# USB_TO_UART.net
KiCad netlist of a schematic drawn in Altium Designer
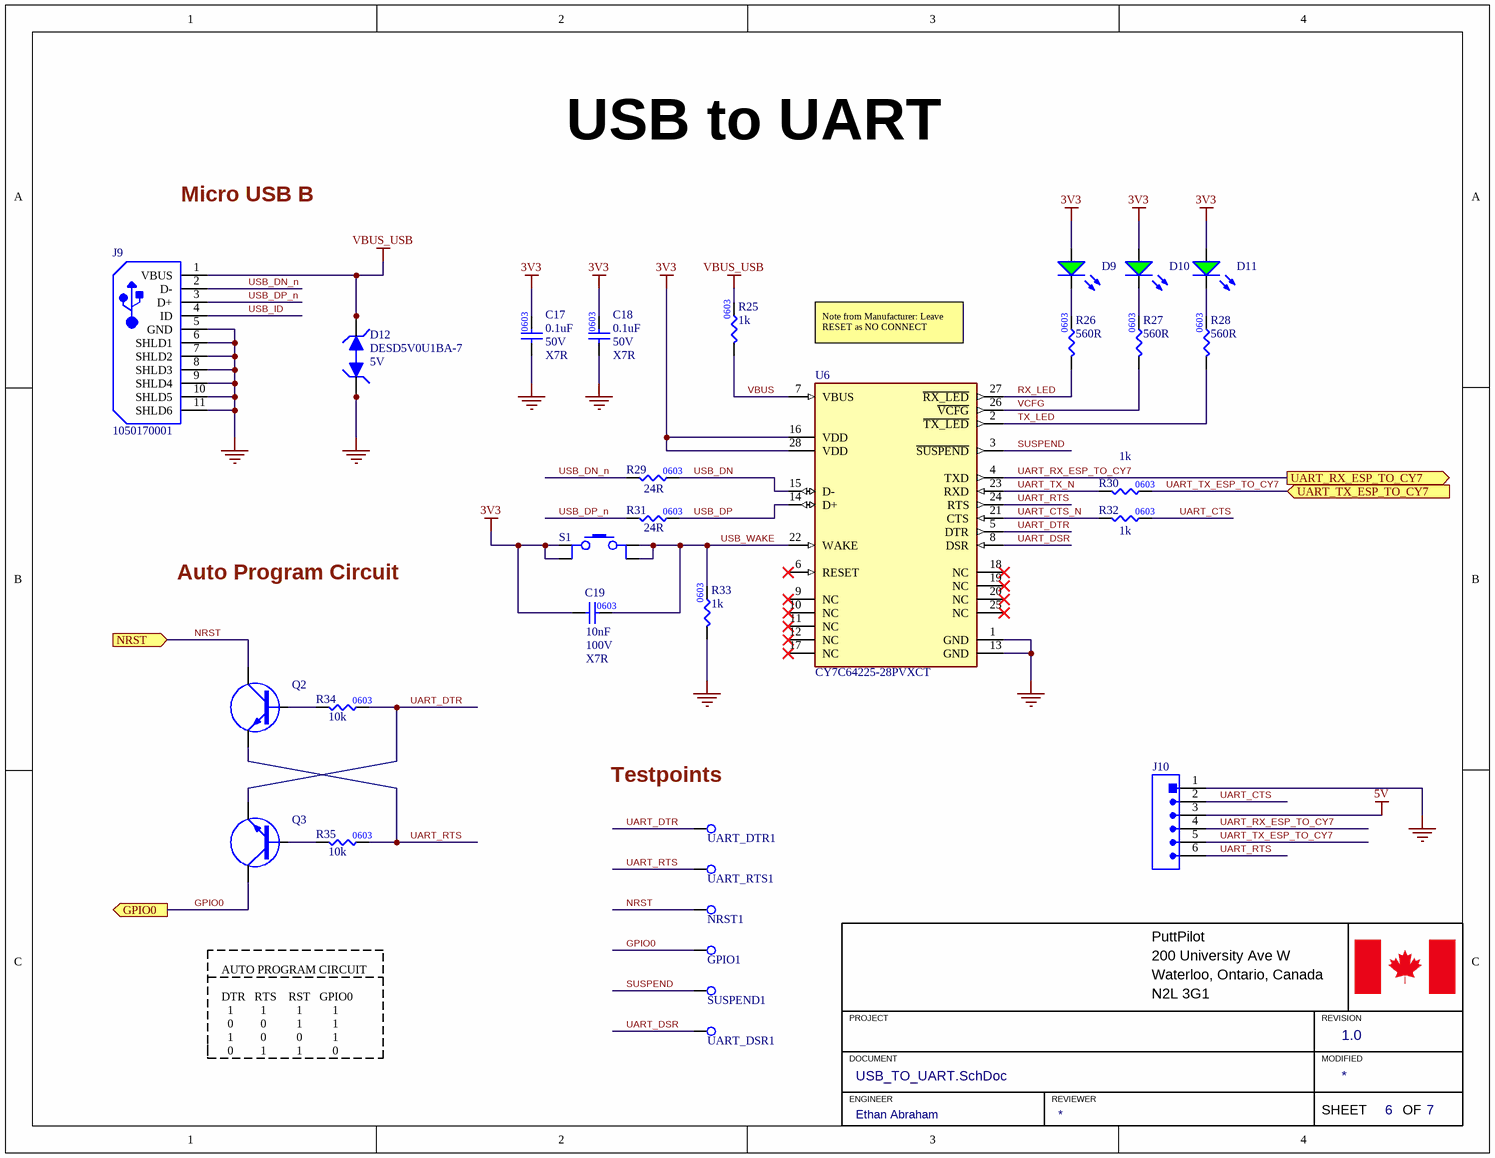
[diagram p0: USB_TO_UART.SchDoc]

(export (version "E")
  (design (tool "Eeschema 10.0.6"))
  (components
    (comp (ref "C17")
      (value "GCJ188R71H104KA12D")
      (footprint ".CAP_0603")
      (description "CAP CER 0.1uF 50V X7R 0603")
      (fields
        (field (name "MANUFACTURER") "Murata")
        (field (name "TEMPERATURE CHARACTERISTICS CODE") "X7R")
        (field (name "RATED DC VOLTAGE (URDC)") "50V")
        (field (name "CAPACITANCE") "0.1uF")
      )
      (libsource (lib "PuttPilot") (part "GCJ188R71H104KA12D"))
    )
    (comp (ref "C18")
      (value "GCJ188R71H104KA12D")
      (footprint ".CAP_0603")
      (description "CAP CER 0.1uF 50V X7R 0603")
      (fields
        (field (name "MANUFACTURER") "Murata")
        (field (name "TEMPERATURE CHARACTERISTICS CODE") "X7R")
        (field (name "RATED DC VOLTAGE (URDC)") "50V")
        (field (name "CAPACITANCE") "0.1uF")
      )
      (libsource (lib "PuttPilot") (part "GCJ188R71H104KA12D"))
    )
    (comp (ref "C19")
      (value "GCM188R72A103KA37D")
      (footprint ".CAP_0603")
      (description "CAP CER 0.01uF 100V X7R")
      (fields
        (field (name "MANUFACTURER") "Murata")
        (field (name "TOLERANCE") "10%")
        (field (name "DIELECTRIC") "X7R")
        (field (name "VOLTAGE RATING") "100V")
        (field (name "CAPACITANCE") "10nF")
      )
      (libsource (lib "PuttPilot") (part "GCM188R72A103KA37D"))
    )
    (comp (ref "D9")
      (value "LTST-C191KGKT")
      (footprint ".LED_0603")
      (description "LED GREEN 2V 0603")
      (fields (field (name "MANUFACTURER") "Vishay Lite-On"))
      (libsource (lib "PuttPilot") (part "LTST-C191KGKT"))
    )
    (comp (ref "D10")
      (value "LTST-C191KGKT")
      (footprint ".LED_0603")
      (description "LED GREEN 2V 0603")
      (fields (field (name "MANUFACTURER") "Vishay Lite-On"))
      (libsource (lib "PuttPilot") (part "LTST-C191KGKT"))
    )
    (comp (ref "D11")
      (value "LTST-C191KGKT")
      (footprint ".LED_0603")
      (description "LED GREEN 2V 0603")
      (fields (field (name "MANUFACTURER") "Vishay Lite-On"))
      (libsource (lib "PuttPilot") (part "LTST-C191KGKT"))
    )
    (comp (ref "D12")
      (value "DESD5V0U1BA-7")
      (footprint "DESD5V0U1BA-7")
      (description "TVS DIODE 5VWM")
      (fields (field (name "MANUFACTURER") "Diodes") (field (name "REP PK REVERSE VOLTAGE-MAX") "5V"))
      (libsource (lib "PuttPilot") (part "DESD5V0U1BA-7"))
    )
    (comp (ref "GPIO1")
      (value "RCWCTE")
      (footprint "RCWCTE")
      (description "SMT Test Point")
      (fields (field (name "MANUFACTURER") "KOA Speer"))
      (libsource (lib "PuttPilot") (part "RCWCTE"))
    )
    (comp (ref "J9")
      (value "1050170001")
      (footprint "USB_MICRO_B")
      (description "CONN USB MICRO B R/A")
      (fields (field (name "MANUFACTURER") "Molex"))
      (libsource (lib "PuttPilot") (part "1050170001"))
    )
    (comp (ref "J10")
      (value "PRPC040SAAN-RC_POS6")
      (footprint "HEADER_6POS_2.54MM")
      (description "CONN HEADER VERT 6POS 2.54MM")
      (libsource (lib "PuttPilot") (part "PRPC040SAAN-RC_POS6"))
    )
    (comp (ref "NRST1")
      (value "RCWCTE")
      (footprint "RCWCTE")
      (description "SMT Test Point")
      (fields (field (name "MANUFACTURER") "KOA Speer"))
      (libsource (lib "PuttPilot") (part "RCWCTE"))
    )
    (comp (ref "Q2")
      (value "MMBT2222A-7-F")
      (footprint ".SOT-23-3")
      (description "NPN BJT 40V 600mA SOT-23")
      (fields (field (name "MANUFACTURER") "Diodes"))
      (libsource (lib "PuttPilot") (part "MMBT2222A-7-F"))
    )
    (comp (ref "Q3")
      (value "MMBT2222A-7-F")
      (footprint ".SOT-23-3")
      (description "NPN BJT 40V 600mA SOT-23")
      (fields (field (name "MANUFACTURER") "Diodes"))
      (libsource (lib "") (part "MMBT2222A-7-F_1"))
    )
    (comp (ref "R25")
      (value "RC0603FR-071KL")
      (footprint ".RES_0603")
      (description "RES 1K OHM 0603")
      (fields
        (field (name "MANUFACTURER") "Yageo")
        (field (name "TOLERANCE") "1%")
        (field (name "RESISTANCE") "1k")
      )
      (libsource (lib "PuttPilot") (part "RC0603FR-071KL"))
    )
    (comp (ref "R26")
      (value "RC0603FR-07560RL")
      (footprint ".RES_0603")
      (description "RES 560 OHM 0603")
      (fields
        (field (name "MANUFACTURER") "Yageo")
        (field (name "TOLERANCE") "1%")
        (field (name "RESISTANCE") "560R")
      )
      (libsource (lib "PuttPilot") (part "RC0603FR-07560RL"))
    )
    (comp (ref "R27")
      (value "RC0603FR-07560RL")
      (footprint ".RES_0603")
      (description "RES 560 OHM 0603")
      (fields
        (field (name "MANUFACTURER") "Yageo")
        (field (name "TOLERANCE") "1%")
        (field (name "RESISTANCE") "560R")
      )
      (libsource (lib "PuttPilot") (part "RC0603FR-07560RL"))
    )
    (comp (ref "R28")
      (value "RC0603FR-07560RL")
      (footprint ".RES_0603")
      (description "RES 560 OHM 0603")
      (fields
        (field (name "MANUFACTURER") "Yageo")
        (field (name "TOLERANCE") "1%")
        (field (name "RESISTANCE") "560R")
      )
      (libsource (lib "PuttPilot") (part "RC0603FR-07560RL"))
    )
    (comp (ref "R29")
      (value "RC0603FR-0724RL")
      (footprint ".RES_0603")
      (description "RES 24 OHM 0603")
      (fields
        (field (name "MANUFACTURER") "Yageo")
        (field (name "TOLERANCE") "1%")
        (field (name "RESISTANCE") "24R")
      )
      (libsource (lib "PuttPilot") (part "RC0603FR-0724RL"))
    )
    (comp (ref "R30")
      (value "RC0603FR-071KL")
      (footprint ".RES_0603")
      (description "RES 1K OHM 0603")
      (fields
        (field (name "MANUFACTURER") "Yageo")
        (field (name "TOLERANCE") "1%")
        (field (name "RESISTANCE") "1k")
      )
      (libsource (lib "PuttPilot") (part "RC0603FR-071KL"))
    )
    (comp (ref "R31")
      (value "RC0603FR-0724RL")
      (footprint ".RES_0603")
      (description "RES 24 OHM 0603")
      (fields
        (field (name "MANUFACTURER") "Yageo")
        (field (name "TOLERANCE") "1%")
        (field (name "RESISTANCE") "24R")
      )
      (libsource (lib "PuttPilot") (part "RC0603FR-0724RL"))
    )
    (comp (ref "R32")
      (value "RC0603FR-071KL")
      (footprint ".RES_0603")
      (description "RES 1K OHM 0603")
      (fields
        (field (name "MANUFACTURER") "Yageo")
        (field (name "TOLERANCE") "1%")
        (field (name "RESISTANCE") "1k")
      )
      (libsource (lib "PuttPilot") (part "RC0603FR-071KL"))
    )
    (comp (ref "R33")
      (value "RC0603FR-071KL")
      (footprint ".RES_0603")
      (description "RES 1K OHM 0603")
      (fields
        (field (name "MANUFACTURER") "Yageo")
        (field (name "TOLERANCE") "1%")
        (field (name "RESISTANCE") "1k")
      )
      (libsource (lib "PuttPilot") (part "RC0603FR-071KL"))
    )
    (comp (ref "R34")
      (value "RC0603FR-0710KL")
      (footprint ".RES_0603")
      (description "RES 10K OHM 0603")
      (fields
        (field (name "MANUFACTURER") "Yageo")
        (field (name "TOLERANCE") "1%")
        (field (name "RESISTANCE") "10k")
      )
      (libsource (lib "PuttPilot") (part "RC0603FR-0710KL"))
    )
    (comp (ref "R35")
      (value "RC0603FR-0710KL")
      (footprint ".RES_0603")
      (description "RES 10K OHM 0603")
      (fields
        (field (name "MANUFACTURER") "Yageo")
        (field (name "TOLERANCE") "1%")
        (field (name "RESISTANCE") "10k")
      )
      (libsource (lib "PuttPilot") (part "RC0603FR-0710KL"))
    )
    (comp (ref "S1")
      (value "PTS647SN38SMTR2LFS")
      (footprint "PTS647SN38SMTR2LFS")
      (description "SWITCH TACTILE SPST-NO 0.05A 12V")
      (fields (field (name "MANUFACTURER") "ITT C&K"))
      (libsource (lib "PuttPilot") (part "PTS647SN38SMTR2LFS"))
    )
    (comp (ref "SUSPEND1")
      (value "RCWCTE")
      (footprint "RCWCTE")
      (description "SMT Test Point")
      (fields (field (name "MANUFACTURER") "KOA Speer"))
      (libsource (lib "PuttPilot") (part "RCWCTE"))
    )
    (comp (ref "U6")
      (value "CY7C64225-28PVXCT")
      (footprint "CY7C64225-28PVXCT")
      (description "USB to UART SOP 28 Pin")
      (fields (field (name "MANUFACTURER") "Infineon"))
      (libsource (lib "PuttPilot") (part "CY7C64225-28PVXCT"))
    )
    (comp (ref "UART_DSR1")
      (value "RCWCTE")
      (footprint "RCWCTE")
      (description "SMT Test Point")
      (fields (field (name "MANUFACTURER") "KOA Speer"))
      (libsource (lib "PuttPilot") (part "RCWCTE"))
    )
    (comp (ref "UART_DTR1")
      (value "RCWCTE")
      (footprint "RCWCTE")
      (description "SMT Test Point")
      (fields (field (name "MANUFACTURER") "KOA Speer"))
      (libsource (lib "PuttPilot") (part "RCWCTE"))
    )
    (comp (ref "UART_RTS1")
      (value "RCWCTE")
      (footprint "RCWCTE")
      (description "SMT Test Point")
      (fields (field (name "MANUFACTURER") "KOA Speer"))
      (libsource (lib "PuttPilot") (part "RCWCTE"))
    )
  )
  (nets
    (net (code "1") (name "/GPIO0") (class "Default")
      (node (ref "GPIO1") (pin "1") (pinfunction "1_1") (pintype "passive"))
      (node (ref "Q3") (pin "2") (pinfunction "Emitter_2") (pintype "passive"))
    )
    (net (code "2") (name "/NRST") (class "Default")
      (node (ref "NRST1") (pin "1") (pinfunction "1_1") (pintype "passive"))
      (node (ref "Q2") (pin "2") (pinfunction "Emitter_2") (pintype "passive"))
    )
    (net (code "3") (name "/RX_LED") (class "Default")
      (node (ref "R26") (pin "1") (pinfunction "1_1") (pintype "passive"))
      (node (ref "U6") (pin "27") (pinfunction "~{RX_LED}_27") (pintype "output"))
    )
    (net (code "4") (name "/SUSPEND") (class "Default")
      (node (ref "SUSPEND1") (pin "1") (pinfunction "1_1") (pintype "passive"))
      (node (ref "U6") (pin "3") (pinfunction "~{SUSPEND}_3") (pintype "output"))
    )
    (net (code "5") (name "/TX_LED") (class "Default")
      (node (ref "R28") (pin "1") (pinfunction "1_1") (pintype "passive"))
      (node (ref "U6") (pin "2") (pinfunction "~{TX_LED}_2") (pintype "output"))
    )
    (net (code "6") (name "/UART_CTS") (class "Default")
      (node (ref "J10") (pin "2") (pinfunction "2_2") (pintype "passive"))
      (node (ref "R32") (pin "2") (pinfunction "2_2") (pintype "passive"))
    )
    (net (code "7") (name "/UART_CTS_N") (class "Default")
      (node (ref "R32") (pin "1") (pinfunction "1_1") (pintype "passive"))
      (node (ref "U6") (pin "21") (pinfunction "CTS_21") (pintype "input"))
    )
    (net (code "8") (name "/UART_DSR") (class "Default")
      (node (ref "U6") (pin "8") (pinfunction "DSR_8") (pintype "input"))
      (node (ref "UART_DSR1") (pin "1") (pinfunction "1_1") (pintype "passive"))
    )
    (net (code "9") (name "/UART_DTR") (class "Default")
      (node (ref "Q3") (pin "3") (pinfunction "Collector_3") (pintype "passive"))
      (node (ref "R34") (pin "2") (pinfunction "2_2") (pintype "passive"))
      (node (ref "U6") (pin "5") (pinfunction "DTR_5") (pintype "output"))
      (node (ref "UART_DTR1") (pin "1") (pinfunction "1_1") (pintype "passive"))
    )
    (net (code "10") (name "/UART_RTS") (class "Default")
      (node (ref "J10") (pin "6") (pinfunction "6_6") (pintype "passive"))
      (node (ref "Q2") (pin "3") (pinfunction "Collector_3") (pintype "passive"))
      (node (ref "R35") (pin "2") (pinfunction "2_2") (pintype "passive"))
      (node (ref "U6") (pin "24") (pinfunction "RTS_24") (pintype "output"))
      (node (ref "UART_RTS1") (pin "1") (pinfunction "1_1") (pintype "passive"))
    )
    (net (code "11") (name "/UART_RX_ESP_TO_CY7") (class "Default")
      (node (ref "J10") (pin "4") (pinfunction "4_4") (pintype "passive"))
      (node (ref "U6") (pin "4") (pinfunction "TXD_4") (pintype "output"))
    )
    (net (code "12") (name "/UART_TX_ESP_TO_CY7") (class "Default")
      (node (ref "J10") (pin "5") (pinfunction "5_5") (pintype "passive"))
      (node (ref "R30") (pin "2") (pinfunction "2_2") (pintype "passive"))
    )
    (net (code "13") (name "/UART_TX_N") (class "Default")
      (node (ref "R30") (pin "1") (pinfunction "1_1") (pintype "passive"))
      (node (ref "U6") (pin "23") (pinfunction "RXD_23") (pintype "input"))
    )
    (net (code "14") (name "/USB_DN") (class "Default")
      (node (ref "R29") (pin "2") (pinfunction "2_2") (pintype "passive"))
      (node (ref "U6") (pin "15") (pinfunction "D-_15") (pintype "bidirectional"))
    )
    (net (code "15") (name "/USB_DN_n") (class "Default")
      (node (ref "J9") (pin "2") (pinfunction "D-_2") (pintype "passive"))
      (node (ref "R29") (pin "1") (pinfunction "1_1") (pintype "passive"))
    )
    (net (code "16") (name "/USB_DP") (class "Default")
      (node (ref "R31") (pin "2") (pinfunction "2_2") (pintype "passive"))
      (node (ref "U6") (pin "14") (pinfunction "D+_14") (pintype "bidirectional"))
    )
    (net (code "17") (name "/USB_DP_n") (class "Default")
      (node (ref "J9") (pin "3") (pinfunction "D+_3") (pintype "passive"))
      (node (ref "R31") (pin "1") (pinfunction "1_1") (pintype "passive"))
    )
    (net (code "18") (name "/USB_ID") (class "Default")
      (node (ref "J9") (pin "4") (pinfunction "ID_4") (pintype "passive"))
    )
    (net (code "19") (name "/USB_WAKE") (class "Default")
      (node (ref "C19") (pin "2") (pinfunction "2_2") (pintype "passive"))
      (node (ref "R33") (pin "2") (pinfunction "2_2") (pintype "passive"))
      (node (ref "S1") (pin "3") (pinfunction "3_3") (pintype "passive"))
      (node (ref "S1") (pin "4") (pinfunction "4_4") (pintype "passive"))
      (node (ref "U6") (pin "22") (pinfunction "WAKE_22") (pintype "input"))
    )
    (net (code "20") (name "/VBUS") (class "Default")
      (node (ref "R25") (pin "1") (pinfunction "1_1") (pintype "passive"))
      (node (ref "U6") (pin "7") (pinfunction "VBUS_7") (pintype "input"))
    )
    (net (code "21") (name "/VCFG") (class "Default")
      (node (ref "R27") (pin "1") (pinfunction "1_1") (pintype "passive"))
      (node (ref "U6") (pin "26") (pinfunction "~{VCFG}_26") (pintype "output"))
    )
    (net (code "22") (name "3V3") (class "Default")
      (node (ref "C17") (pin "2") (pinfunction "2_2") (pintype "passive"))
      (node (ref "C18") (pin "2") (pinfunction "2_2") (pintype "passive"))
      (node (ref "C19") (pin "1") (pinfunction "1_1") (pintype "passive"))
      (node (ref "D10") (pin "1") (pinfunction "A_1") (pintype "passive"))
      (node (ref "D11") (pin "1") (pinfunction "A_1") (pintype "passive"))
      (node (ref "D9") (pin "1") (pinfunction "A_1") (pintype "passive"))
      (node (ref "S1") (pin "1") (pinfunction "1_1") (pintype "passive"))
      (node (ref "S1") (pin "2") (pinfunction "2_2") (pintype "passive"))
      (node (ref "U6") (pin "16") (pinfunction "VDD_16") (pintype "power_in"))
      (node (ref "U6") (pin "28") (pinfunction "VDD_28") (pintype "power_in"))
    )
    (net (code "23") (name "5V") (class "Default")
      (node (ref "J10") (pin "3") (pinfunction "3_3") (pintype "passive"))
    )
    (net (code "24") (name "GND") (class "Default")
      (node (ref "C17") (pin "1") (pinfunction "1_1") (pintype "passive"))
      (node (ref "C18") (pin "1") (pinfunction "1_1") (pintype "passive"))
      (node (ref "D12") (pin "1") (pinfunction "Pin_1_1") (pintype "passive"))
      (node (ref "J10") (pin "1") (pinfunction "1_1") (pintype "passive"))
      (node (ref "J9") (pin "10") (pinfunction "SHLD5_10") (pintype "passive"))
      (node (ref "J9") (pin "11") (pinfunction "SHLD6_11") (pintype "passive"))
      (node (ref "J9") (pin "5") (pinfunction "GND_5") (pintype "passive"))
      (node (ref "J9") (pin "6") (pinfunction "SHLD1_6") (pintype "passive"))
      (node (ref "J9") (pin "7") (pinfunction "SHLD2_7") (pintype "passive"))
      (node (ref "J9") (pin "8") (pinfunction "SHLD3_8") (pintype "passive"))
      (node (ref "J9") (pin "9") (pinfunction "SHLD4_9") (pintype "passive"))
      (node (ref "R33") (pin "1") (pinfunction "1_1") (pintype "passive"))
      (node (ref "U6") (pin "1") (pinfunction "GND_1") (pintype "power_in"))
      (node (ref "U6") (pin "13") (pinfunction "GND_13") (pintype "power_in"))
    )
    (net (code "25") (name "Net-(D9-K)") (class "Default")
      (node (ref "D9") (pin "2") (pinfunction "K_2") (pintype "passive"))
      (node (ref "R26") (pin "2") (pinfunction "2_2") (pintype "passive"))
    )
    (net (code "26") (name "Net-(D10-K)") (class "Default")
      (node (ref "D10") (pin "2") (pinfunction "K_2") (pintype "passive"))
      (node (ref "R27") (pin "2") (pinfunction "2_2") (pintype "passive"))
    )
    (net (code "27") (name "Net-(D11-K)") (class "Default")
      (node (ref "D11") (pin "2") (pinfunction "K_2") (pintype "passive"))
      (node (ref "R28") (pin "2") (pinfunction "2_2") (pintype "passive"))
    )
    (net (code "28") (name "Net-(Q2-Base)") (class "Default")
      (node (ref "Q2") (pin "1") (pinfunction "Base_1") (pintype "passive"))
      (node (ref "R34") (pin "1") (pinfunction "1_1") (pintype "passive"))
    )
    (net (code "29") (name "Net-(Q3-Base)") (class "Default")
      (node (ref "Q3") (pin "1") (pinfunction "Base_1") (pintype "passive"))
      (node (ref "R35") (pin "1") (pinfunction "1_1") (pintype "passive"))
    )
    (net (code "30") (name "VBUS_USB") (class "Default")
      (node (ref "D12") (pin "2") (pinfunction "Pin_2_2") (pintype "passive"))
      (node (ref "J9") (pin "1") (pinfunction "VBUS_1") (pintype "passive"))
      (node (ref "R25") (pin "2") (pinfunction "2_2") (pintype "passive"))
    )
    (net (code "31") (name "unconnected-(U6-NC-Pad9)") (class "Default")
      (node (ref "U6") (pin "9") (pinfunction "NC_9") (pintype "passive+no_connect"))
    )
    (net (code "32") (name "unconnected-(U6-NC-Pad10)") (class "Default")
      (node (ref "U6") (pin "10") (pinfunction "NC_10") (pintype "passive+no_connect"))
    )
    (net (code "33") (name "unconnected-(U6-NC-Pad11)") (class "Default")
      (node (ref "U6") (pin "11") (pinfunction "NC_11") (pintype "passive+no_connect"))
    )
    (net (code "34") (name "unconnected-(U6-NC-Pad12)") (class "Default")
      (node (ref "U6") (pin "12") (pinfunction "NC_12") (pintype "passive+no_connect"))
    )
    (net (code "35") (name "unconnected-(U6-NC-Pad17)") (class "Default")
      (node (ref "U6") (pin "17") (pinfunction "NC_17") (pintype "passive+no_connect"))
    )
    (net (code "36") (name "unconnected-(U6-NC-Pad18)") (class "Default")
      (node (ref "U6") (pin "18") (pinfunction "NC_18") (pintype "passive+no_connect"))
    )
    (net (code "37") (name "unconnected-(U6-NC-Pad19)") (class "Default")
      (node (ref "U6") (pin "19") (pinfunction "NC_19") (pintype "passive+no_connect"))
    )
    (net (code "38") (name "unconnected-(U6-NC-Pad20)") (class "Default")
      (node (ref "U6") (pin "20") (pinfunction "NC_20") (pintype "passive+no_connect"))
    )
    (net (code "39") (name "unconnected-(U6-NC-Pad25)") (class "Default")
      (node (ref "U6") (pin "25") (pinfunction "NC_25") (pintype "passive+no_connect"))
    )
    (net (code "40") (name "unconnected-(U6-RESET-Pad6)") (class "Default")
      (node (ref "U6") (pin "6") (pinfunction "RESET_6") (pintype "input+no_connect"))
    )
  )
)
